# ws2812esp32_v1_0.net
KiCad netlist of a schematic drawn in Altium Designer
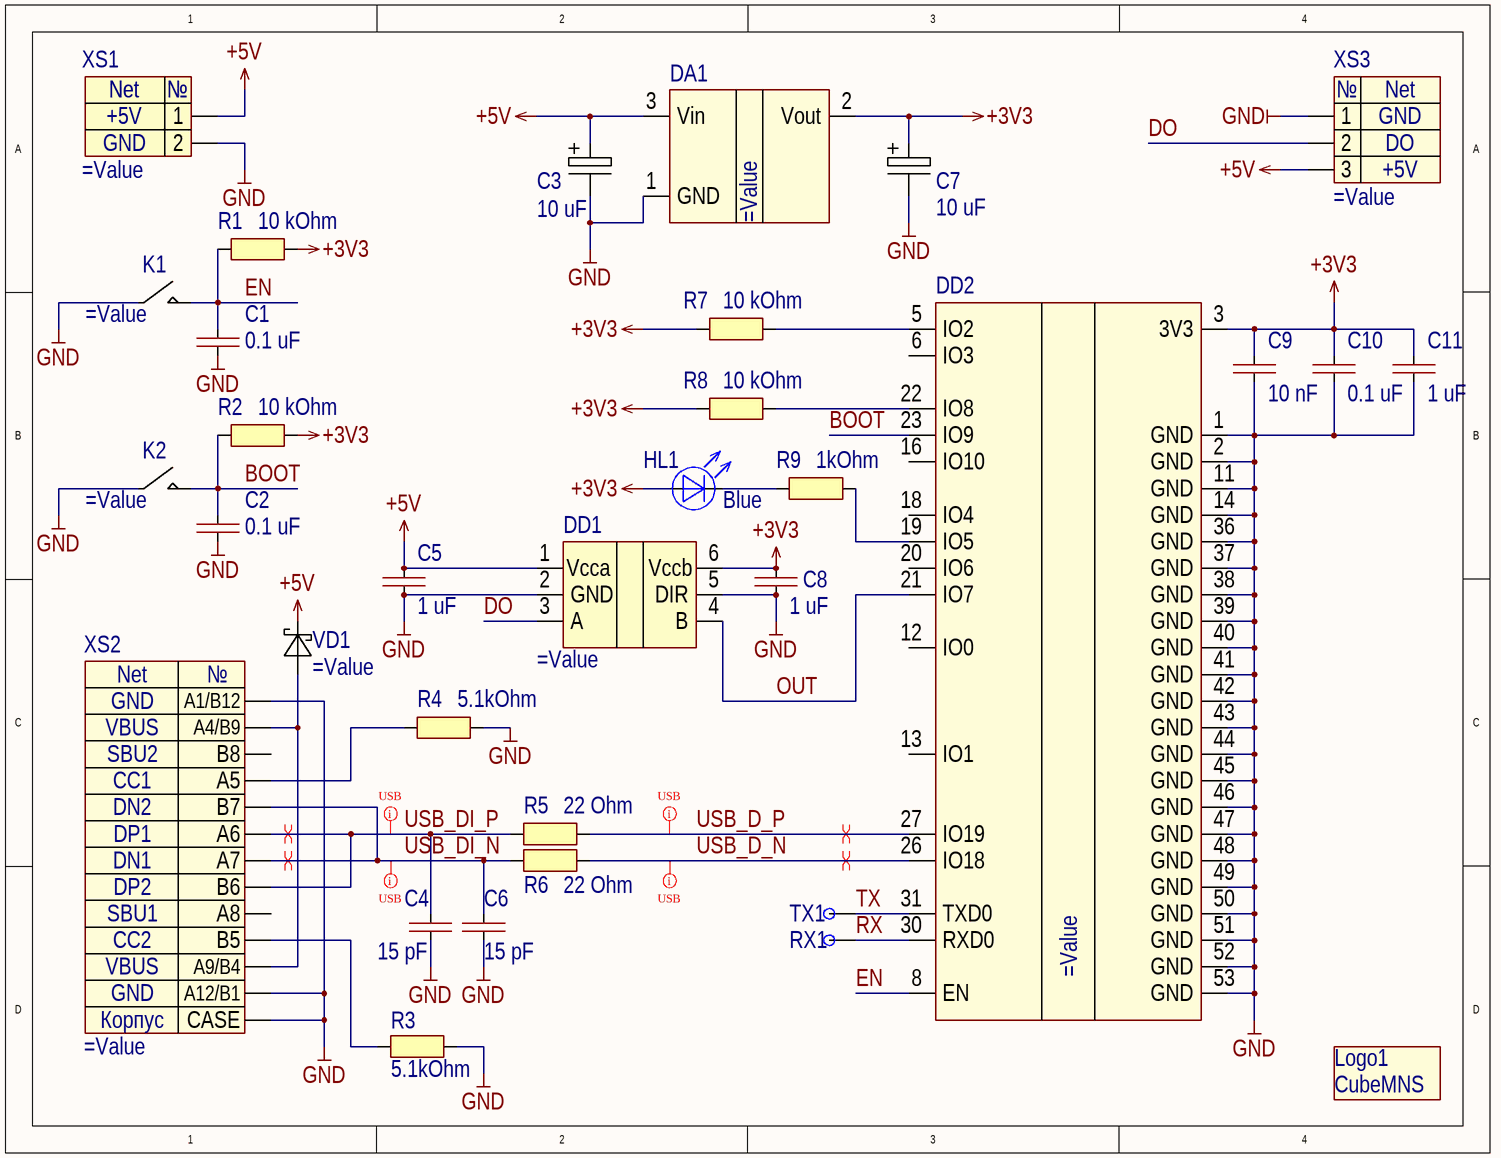
[diagram p0: ws2812esp32_v1.0.SchDoc]

(export (version "E")
  (design (tool "Eeschema 10.0.6"))
  (components
    (comp (ref "C1")
      (value "0.1 uF")
      (footprint "C0402")
      (description "CAP CER 0.1UF 50V X7R 0402")
      (fields (field (name "PART NUMBER") "GRM155R71H104KE14D") (field (name "TOLERANCE") "10"))
      (libsource (lib "ws2812esp32_v1.0_Schlib") (part "C0402 0.1uF 10% 25V"))
    )
    (comp (ref "C2")
      (value "0.1 uF")
      (footprint "C0402")
      (description "CAP CER 0.1UF 50V X7R 0402")
      (fields (field (name "PART NUMBER") "GRM155R71H104KE14D") (field (name "TOLERANCE") "10"))
      (libsource (lib "ws2812esp32_v1.0_Schlib") (part "C0402 0.1uF 10% 25V"))
    )
    (comp (ref "C3")
      (value "10 uF")
      (footprint "C tantalin Type A")
      (description "CAP TANT 10UF 10% 10V 1206")
      (fields (field (name "PART NUMBER") "T491A106K010AT") (field (name "TOLERANCE") "10%"))
      (libsource (lib "ws2812esp32_v1.0_Schlib") (part "C tantalum type A 10uF"))
    )
    (comp (ref "C4")
      (value "15 pF")
      (footprint "C0402")
      (description "CAP CER 15PF 50V C0G/NP0 0402")
      (fields (field (name "PART NUMBER") "GRM1555C1H150JA01D") (field (name "TOLERANCE") "5"))
      (libsource (lib "ws2812esp32_v1.0_Schlib") (part "C0402 15pF 5% 25V"))
    )
    (comp (ref "C5")
      (value "1 uF")
      (footprint "C0402")
      (description "CAP CER 1UF 25V X5R 0402")
      (fields (field (name "PART NUMBER") "GRM155R61E105KA12D") (field (name "VOLTAGE") "25V"))
      (libsource (lib "ws2812esp32_v1.0_Schlib") (part "C0402 1uF 10% 25V"))
    )
    (comp (ref "C6")
      (value "15 pF")
      (footprint "C0402")
      (description "CAP CER 15PF 50V C0G/NP0 0402")
      (fields (field (name "PART NUMBER") "GRM1555C1H150JA01D") (field (name "TOLERANCE") "5"))
      (libsource (lib "ws2812esp32_v1.0_Schlib") (part "C0402 15pF 5% 25V"))
    )
    (comp (ref "C7")
      (value "10 uF")
      (footprint "C tantalin Type A")
      (description "CAP TANT 10UF 10% 10V 1206")
      (fields (field (name "PART NUMBER") "T491A106K010AT") (field (name "TOLERANCE") "10%"))
      (libsource (lib "ws2812esp32_v1.0_Schlib") (part "C tantalum type A 10uF"))
    )
    (comp (ref "C8")
      (value "1 uF")
      (footprint "C0402")
      (description "CAP CER 1UF 25V X5R 0402")
      (fields (field (name "PART NUMBER") "GRM155R61E105KA12D") (field (name "VOLTAGE") "25V"))
      (libsource (lib "ws2812esp32_v1.0_Schlib") (part "C0402 1uF 10% 25V"))
    )
    (comp (ref "C9")
      (value "10 nF")
      (footprint "C0402")
      (description "CAP CER 10000PF 25V X7R 0402")
      (fields (field (name "PART NUMBER") "GRM155R71E103KA01D") (field (name "TOLERANCE") "10%"))
      (libsource (lib "ws2812esp32_v1.0_Schlib") (part "C0402 10nF 10% 25V"))
    )
    (comp (ref "C10")
      (value "0.1 uF")
      (footprint "C0402")
      (description "CAP CER 0.1UF 50V X7R 0402")
      (fields (field (name "PART NUMBER") "GRM155R71H104KE14D") (field (name "TOLERANCE") "10"))
      (libsource (lib "ws2812esp32_v1.0_Schlib") (part "C0402 0.1uF 10% 25V"))
    )
    (comp (ref "C11")
      (value "1 uF")
      (footprint "C0402")
      (description "CAP CER 1UF 25V X5R 0402")
      (fields (field (name "PART NUMBER") "GRM155R61E105KA12D") (field (name "VOLTAGE") "25V"))
      (libsource (lib "ws2812esp32_v1.0_Schlib") (part "C0402 1uF 10% 25V"))
    )
    (comp (ref "DA1")
      (value "~")
      (footprint "SOT223")
      (description "IC REG LINEAR 3.3V 1A SOT223-3")
      (fields (field (name "PART NUMBER") "LM1117GS-3.3") (field (name "VOLTAGE") "+3.3V"))
      (libsource (lib "ws2812esp32_v1.0_Schlib") (part "LM1117GS-3.3"))
    )
    (comp (ref "DD1")
      (value "~")
      (footprint "SC-70-6")
      (description "IC TRANSLTR BIDIRECTIONAL SC70-6")
      (fields (field (name "PART NUMBER") "SN74LVC1T45DCK") (field (name "VOLTAGE") "+5.5V"))
      (libsource (lib "ws2812esp32_v1.0_Schlib") (part "SN74LVC1T45DCK"))
    )
    (comp (ref "DD2")
      (value "~")
      (footprint "ESP32-C3-MINI-1")
      (description "RF TXRX MODULE BT PCB TRACE SMD")
      (fields (field (name "PART NUMBER") "ESP32-C3-MINI-1") (field (name "VOLTAGE") "+3.3V"))
      (libsource (lib "ws2812esp32_v1.0_Schlib") (part "ESP32-C3-MINI-1"))
    )
    (comp (ref "HL1")
      (value "Blue")
      (footprint "LED0603")
      (description "LED 0603 Blue")
      (fields (field (name "PART NUMBER") "APT1608QBC/D") (field (name "VOLTAGE") "4V"))
      (libsource (lib "ws2812esp32_v1.0_Schlib") (part "LED 0603 Blue"))
    )
    (comp (ref "K1")
      (value "~")
      (footprint "B3U-1000P-B")
      (description "SWITCH TACTILE SPST-NO 0.05A 12V")
      (fields (field (name "PART NUMBER") "B3U-1000P-B"))
      (libsource (lib "ws2812esp32_v1.0_Schlib") (part "B3U-1000P-B"))
    )
    (comp (ref "K2")
      (value "~")
      (footprint "B3U-1000P-B")
      (description "SWITCH TACTILE SPST-NO 0.05A 12V")
      (fields (field (name "PART NUMBER") "B3U-1000P-B"))
      (libsource (lib "ws2812esp32_v1.0_Schlib") (part "B3U-1000P-B"))
    )
    (comp (ref "Logo1")
      (value "CubeMNS")
      (footprint "CubeMNS")
      (libsource (lib "ws2812esp32_v1.0_Schlib") (part "CubeMNS"))
    )
    (comp (ref "R1")
      (value "10 kOhm")
      (footprint "R0402")
      (description "RES 10K OHM 1/16W 1% 0402 SMD")
      (fields (field (name "PART NUMBER") "RC0402FR-0710KL") (field (name "TOLERANCE") "1%"))
      (libsource (lib "ws2812esp32_v1.0_Schlib") (part "R0402 10kOhm 1%"))
    )
    (comp (ref "R2")
      (value "10 kOhm")
      (footprint "R0402")
      (description "RES 10K OHM 1/16W 1% 0402 SMD")
      (fields (field (name "PART NUMBER") "RC0402FR-0710KL") (field (name "TOLERANCE") "1%"))
      (libsource (lib "ws2812esp32_v1.0_Schlib") (part "R0402 10kOhm 1%"))
    )
    (comp (ref "R3")
      (value "5.1kOhm")
      (footprint "R0402")
      (description "RES 5.1K OHM 1/16W 1% 0402 SMD")
      (fields (field (name "PART NUMBER") "RC0402FR-075K1L") (field (name "TOLERANCE") "1%"))
      (libsource (lib "ws2812esp32_v1.0_Schlib") (part "R0402 5.1kOhm 1%"))
    )
    (comp (ref "R4")
      (value "5.1kOhm")
      (footprint "R0402")
      (description "RES 5.1K OHM 1/16W 1% 0402 SMD")
      (fields (field (name "PART NUMBER") "RC0402FR-075K1L") (field (name "TOLERANCE") "1%"))
      (libsource (lib "ws2812esp32_v1.0_Schlib") (part "R0402 5.1kOhm 1%"))
    )
    (comp (ref "R5")
      (value "22 Ohm")
      (footprint "R0402")
      (description "RES 22 OHM 1/16W 1% 0402 SMD")
      (fields (field (name "PART NUMBER") "RC0402FR-0722RL") (field (name "TOLERANCE") "1%"))
      (libsource (lib "ws2812esp32_v1.0_Schlib") (part "R0402 22Ohm 1%"))
    )
    (comp (ref "R6")
      (value "22 Ohm")
      (footprint "R0402")
      (description "RES 22 OHM 1/16W 1% 0402 SMD")
      (fields (field (name "PART NUMBER") "RC0402FR-0722RL") (field (name "TOLERANCE") "1%"))
      (libsource (lib "ws2812esp32_v1.0_Schlib") (part "R0402 22Ohm 1%"))
    )
    (comp (ref "R7")
      (value "10 kOhm")
      (footprint "R0402")
      (description "RES 10K OHM 1/16W 1% 0402 SMD")
      (fields (field (name "PART NUMBER") "RC0402FR-0710KL") (field (name "TOLERANCE") "1%"))
      (libsource (lib "ws2812esp32_v1.0_Schlib") (part "R0402 10kOhm 1%"))
    )
    (comp (ref "R8")
      (value "10 kOhm")
      (footprint "R0402")
      (description "RES 10K OHM 1/16W 1% 0402 SMD")
      (fields (field (name "PART NUMBER") "RC0402FR-0710KL") (field (name "TOLERANCE") "1%"))
      (libsource (lib "ws2812esp32_v1.0_Schlib") (part "R0402 10kOhm 1%"))
    )
    (comp (ref "R9")
      (value "1kOhm")
      (footprint "R0402")
      (description "RES 1K OHM 1/16W 1% 0402 SMD")
      (fields (field (name "PART NUMBER") "RC0402FR-071KL") (field (name "TOLERANCE") "1%"))
      (libsource (lib "ws2812esp32_v1.0_Schlib") (part "R0402 1kOhm 1%"))
    )
    (comp (ref "RX1")
      (value "~")
      (footprint "СontactPad0.5")
      (description "Round 0.5 mm")
      (libsource (lib "ws2812esp32_v1.0_Schlib") (part "Сontact Pad"))
    )
    (comp (ref "TX1")
      (value "~")
      (footprint "СontactPad0.5")
      (description "Round 0.5 mm")
      (libsource (lib "ws2812esp32_v1.0_Schlib") (part "Сontact Pad"))
    )
    (comp (ref "VD1")
      (value "~")
      (footprint "SOD-123F")
      (description "DIODE SCHOTTKY 40V 1A")
      (fields (field (name "PART NUMBER") "DSK14") (field (name "VOLTAGE") "40V"))
      (libsource (lib "ws2812esp32_v1.0_Schlib") (part "DSK14"))
    )
    (comp (ref "XS1")
      (value "~")
      (footprint "FLTS22WR00")
      (description "SMD TERMINAL BLOCK 2 PIN")
      (fields (field (name "PART NUMBER") "FLTS22WR00") (field (name "VOLTAGE") "250V"))
      (libsource (lib "ws2812esp32_v1.0_Schlib") (part "FLTS22WR00"))
    )
    (comp (ref "XS2")
      (value "~")
      (footprint "USB4110-GF-A")
      (description "CONN RCP USB2.0 TYP C 24P SMD RA")
      (fields (field (name "PART NUMBER") "USB4110-GF-A") (field (name "VOLTAGE") "48V"))
      (libsource (lib "ws2812esp32_v1.0_Schlib") (part "USB4110-GF-A"))
    )
    (comp (ref "XS3")
      (value "~")
      (footprint "FLTS32WR00")
      (description "SMD TERMINAL BLOCK 3 PIN")
      (fields (field (name "PART NUMBER") "FLTS32WR00") (field (name "VOLTAGE") "250V"))
      (libsource (lib "ws2812esp32_v1.0_Schlib") (part "FLTS32WR00"))
    )
  )
  (nets
    (net (code "1") (name "+3V3") (class "Default")
      (node (ref "C10") (pin "2") (pinfunction "2_2") (pintype "passive"))
      (node (ref "C11") (pin "2") (pinfunction "2_2") (pintype "passive"))
      (node (ref "C7") (pin "1") (pinfunction "+_1") (pintype "passive"))
      (node (ref "C8") (pin "2") (pinfunction "2_2") (pintype "passive"))
      (node (ref "C9") (pin "2") (pinfunction "2_2") (pintype "passive"))
      (node (ref "DA1") (pin "2") (pinfunction "Vout_2") (pintype "passive"))
      (node (ref "DD1") (pin "6") (pinfunction "Vccb_6") (pintype "passive"))
      (node (ref "DD2") (pin "3") (pinfunction "3V3_3") (pintype "passive"))
      (node (ref "HL1") (pin "2") (pinfunction "+_2") (pintype "passive"))
      (node (ref "R1") (pin "1") (pinfunction "1_1") (pintype "passive"))
      (node (ref "R2") (pin "1") (pinfunction "1_1") (pintype "passive"))
      (node (ref "R7") (pin "2") (pinfunction "2_2") (pintype "passive"))
      (node (ref "R8") (pin "2") (pinfunction "2_2") (pintype "passive"))
    )
    (net (code "2") (name "+5V") (class "Default")
      (node (ref "C3") (pin "1") (pinfunction "+_1") (pintype "passive"))
      (node (ref "C5") (pin "2") (pinfunction "2_2") (pintype "passive"))
      (node (ref "DA1") (pin "3") (pinfunction "Vin_3") (pintype "passive"))
      (node (ref "DD1") (pin "1") (pinfunction "Vcca_1") (pintype "passive"))
      (node (ref "VD1") (pin "1") (pinfunction "-_1") (pintype "passive"))
      (node (ref "XS1") (pin "1") (pinfunction "1_1") (pintype "passive"))
      (node (ref "XS3") (pin "3") (pinfunction "3_3") (pintype "passive"))
    )
    (net (code "3") (name "/BOOT") (class "Default")
      (node (ref "C2") (pin "2") (pinfunction "2_2") (pintype "passive"))
      (node (ref "DD2") (pin "23") (pinfunction "IO9_23") (pintype "passive"))
      (node (ref "K2") (pin "2") (pinfunction "2_2") (pintype "passive"))
      (node (ref "R2") (pin "2") (pinfunction "2_2") (pintype "passive"))
    )
    (net (code "4") (name "/DO") (class "Default")
      (node (ref "DD1") (pin "3") (pinfunction "A_3") (pintype "passive"))
      (node (ref "XS3") (pin "2") (pinfunction "2_2") (pintype "passive"))
    )
    (net (code "5") (name "/EN") (class "Default")
      (node (ref "C1") (pin "2") (pinfunction "2_2") (pintype "passive"))
      (node (ref "DD2") (pin "8") (pinfunction "EN_8") (pintype "passive"))
      (node (ref "K1") (pin "2") (pinfunction "2_2") (pintype "passive"))
      (node (ref "R1") (pin "2") (pinfunction "2_2") (pintype "passive"))
    )
    (net (code "6") (name "/OUT") (class "Default")
      (node (ref "DD1") (pin "4") (pinfunction "B_4") (pintype "passive"))
      (node (ref "DD2") (pin "21") (pinfunction "IO7_21") (pintype "passive"))
    )
    (net (code "7") (name "/RX") (class "Default")
      (node (ref "DD2") (pin "30") (pinfunction "RXD0_30") (pintype "passive"))
      (node (ref "RX1") (pin "1") (pinfunction "1_1") (pintype "passive"))
    )
    (net (code "8") (name "/TX") (class "Default")
      (node (ref "DD2") (pin "31") (pinfunction "TXD0_31") (pintype "passive"))
      (node (ref "TX1") (pin "1") (pinfunction "1_1") (pintype "passive"))
    )
    (net (code "9") (name "/USB_DI_N") (class "Default")
      (node (ref "C6") (pin "2") (pinfunction "2_2") (pintype "passive"))
      (node (ref "R6") (pin "1") (pinfunction "1_1") (pintype "passive"))
      (node (ref "XS2") (pin "A7") (pinfunction "A7_A7") (pintype "passive"))
      (node (ref "XS2") (pin "B7") (pinfunction "B7_B7") (pintype "passive"))
    )
    (net (code "10") (name "/USB_DI_P") (class "Default")
      (node (ref "C4") (pin "2") (pinfunction "2_2") (pintype "passive"))
      (node (ref "R5") (pin "1") (pinfunction "1_1") (pintype "passive"))
      (node (ref "XS2") (pin "A6") (pinfunction "A6_A6") (pintype "passive"))
      (node (ref "XS2") (pin "B6") (pinfunction "B6_B6") (pintype "passive"))
    )
    (net (code "11") (name "/USB_D_N") (class "Default")
      (node (ref "DD2") (pin "26") (pinfunction "IO18_26") (pintype "passive"))
      (node (ref "R6") (pin "2") (pinfunction "2_2") (pintype "passive"))
    )
    (net (code "12") (name "/USB_D_P") (class "Default")
      (node (ref "DD2") (pin "27") (pinfunction "IO19_27") (pintype "passive"))
      (node (ref "R5") (pin "2") (pinfunction "2_2") (pintype "passive"))
    )
    (net (code "13") (name "GND") (class "Default")
      (node (ref "C1") (pin "1") (pinfunction "1_1") (pintype "passive"))
      (node (ref "C10") (pin "1") (pinfunction "1_1") (pintype "passive"))
      (node (ref "C11") (pin "1") (pinfunction "1_1") (pintype "passive"))
      (node (ref "C2") (pin "1") (pinfunction "1_1") (pintype "passive"))
      (node (ref "C3") (pin "2") (pinfunction "-_2") (pintype "passive"))
      (node (ref "C4") (pin "1") (pinfunction "1_1") (pintype "passive"))
      (node (ref "C5") (pin "1") (pinfunction "1_1") (pintype "passive"))
      (node (ref "C6") (pin "1") (pinfunction "1_1") (pintype "passive"))
      (node (ref "C7") (pin "2") (pinfunction "-_2") (pintype "passive"))
      (node (ref "C8") (pin "1") (pinfunction "1_1") (pintype "passive"))
      (node (ref "C9") (pin "1") (pinfunction "1_1") (pintype "passive"))
      (node (ref "DA1") (pin "1") (pinfunction "GND_1") (pintype "passive"))
      (node (ref "DD1") (pin "2") (pinfunction "GND_2") (pintype "passive"))
      (node (ref "DD1") (pin "5") (pinfunction "DIR_5") (pintype "passive"))
      (node (ref "DD2") (pin "1") (pinfunction "GND_1") (pintype "passive"))
      (node (ref "DD2") (pin "11") (pinfunction "GND_11") (pintype "passive"))
      (node (ref "DD2") (pin "14") (pinfunction "GND_14") (pintype "passive"))
      (node (ref "DD2") (pin "2") (pinfunction "GND_2") (pintype "passive"))
      (node (ref "DD2") (pin "36") (pinfunction "GND_36") (pintype "passive"))
      (node (ref "DD2") (pin "37") (pinfunction "GND_37") (pintype "passive"))
      (node (ref "DD2") (pin "38") (pinfunction "GND_38") (pintype "passive"))
      (node (ref "DD2") (pin "39") (pinfunction "GND_39") (pintype "passive"))
      (node (ref "DD2") (pin "40") (pinfunction "GND_40") (pintype "passive"))
      (node (ref "DD2") (pin "41") (pinfunction "GND_41") (pintype "passive"))
      (node (ref "DD2") (pin "42") (pinfunction "GND_42") (pintype "passive"))
      (node (ref "DD2") (pin "43") (pinfunction "GND_43") (pintype "passive"))
      (node (ref "DD2") (pin "44") (pinfunction "GND_44") (pintype "passive"))
      (node (ref "DD2") (pin "45") (pinfunction "GND_45") (pintype "passive"))
      (node (ref "DD2") (pin "46") (pinfunction "GND_46") (pintype "passive"))
      (node (ref "DD2") (pin "47") (pinfunction "GND_47") (pintype "passive"))
      (node (ref "DD2") (pin "48") (pinfunction "GND_48") (pintype "passive"))
      (node (ref "DD2") (pin "49") (pinfunction "GND_49") (pintype "passive"))
      (node (ref "DD2") (pin "50") (pinfunction "GND_50") (pintype "passive"))
      (node (ref "DD2") (pin "51") (pinfunction "GND_51") (pintype "passive"))
      (node (ref "DD2") (pin "52") (pinfunction "GND_52") (pintype "passive"))
      (node (ref "DD2") (pin "53") (pinfunction "GND_53") (pintype "passive"))
      (node (ref "K1") (pin "1") (pinfunction "1_1") (pintype "passive"))
      (node (ref "K2") (pin "1") (pinfunction "1_1") (pintype "passive"))
      (node (ref "R3") (pin "2") (pinfunction "2_2") (pintype "passive"))
      (node (ref "R4") (pin "2") (pinfunction "2_2") (pintype "passive"))
      (node (ref "XS1") (pin "2") (pinfunction "2_2") (pintype "passive"))
      (node (ref "XS2") (pin "0") (pinfunction "CASE_0") (pintype "passive"))
      (node (ref "XS2") (pin "A1/B12") (pinfunction "A1/B12_A1/B12") (pintype "passive"))
      (node (ref "XS2") (pin "A12/B1") (pinfunction "A12/B1_A12/B1") (pintype "passive"))
      (node (ref "XS3") (pin "1") (pinfunction "1_1") (pintype "passive"))
    )
    (net (code "14") (name "Net-(DD2-IO2)") (class "Default")
      (node (ref "DD2") (pin "5") (pinfunction "IO2_5") (pintype "passive"))
      (node (ref "R7") (pin "1") (pinfunction "1_1") (pintype "passive"))
    )
    (net (code "15") (name "Net-(DD2-IO5)") (class "Default")
      (node (ref "DD2") (pin "19") (pinfunction "IO5_19") (pintype "passive"))
      (node (ref "R9") (pin "2") (pinfunction "2_2") (pintype "passive"))
    )
    (net (code "16") (name "Net-(DD2-IO8)") (class "Default")
      (node (ref "DD2") (pin "22") (pinfunction "IO8_22") (pintype "passive"))
      (node (ref "R8") (pin "1") (pinfunction "1_1") (pintype "passive"))
    )
    (net (code "17") (name "Net-(HL1--)") (class "Default")
      (node (ref "HL1") (pin "1") (pinfunction "-_1") (pintype "passive"))
      (node (ref "R9") (pin "1") (pinfunction "1_1") (pintype "passive"))
    )
    (net (code "18") (name "Net-(R3-Pad1)") (class "Default")
      (node (ref "R3") (pin "1") (pinfunction "1_1") (pintype "passive"))
      (node (ref "XS2") (pin "B5") (pinfunction "B5_B5") (pintype "passive"))
    )
    (net (code "19") (name "Net-(R4-Pad1)") (class "Default")
      (node (ref "R4") (pin "1") (pinfunction "1_1") (pintype "passive"))
      (node (ref "XS2") (pin "A5") (pinfunction "A5_A5") (pintype "passive"))
    )
    (net (code "20") (name "Net-(VD1-+)") (class "Default")
      (node (ref "VD1") (pin "2") (pinfunction "+_2") (pintype "passive"))
      (node (ref "XS2") (pin "A4/B9") (pinfunction "A4/B9_A4/B9") (pintype "passive"))
      (node (ref "XS2") (pin "A9/B4") (pinfunction "A9/B4_A9/B4") (pintype "passive"))
    )
    (net (code "21") (name "unconnected-(DD2-IO0-Pad12)") (class "Default")
      (node (ref "DD2") (pin "12") (pinfunction "IO0_12") (pintype "passive"))
    )
    (net (code "22") (name "unconnected-(DD2-IO1-Pad13)") (class "Default")
      (node (ref "DD2") (pin "13") (pinfunction "IO1_13") (pintype "passive"))
    )
    (net (code "23") (name "unconnected-(DD2-IO3-Pad6)") (class "Default")
      (node (ref "DD2") (pin "6") (pinfunction "IO3_6") (pintype "passive"))
    )
    (net (code "24") (name "unconnected-(DD2-IO4-Pad18)") (class "Default")
      (node (ref "DD2") (pin "18") (pinfunction "IO4_18") (pintype "passive"))
    )
    (net (code "25") (name "unconnected-(DD2-IO6-Pad20)") (class "Default")
      (node (ref "DD2") (pin "20") (pinfunction "IO6_20") (pintype "passive"))
    )
    (net (code "26") (name "unconnected-(DD2-IO10-Pad16)") (class "Default")
      (node (ref "DD2") (pin "16") (pinfunction "IO10_16") (pintype "passive"))
    )
    (net (code "27") (name "unconnected-(XS2-PadA8)") (class "Default")
      (node (ref "XS2") (pin "A8") (pinfunction "A8_A8") (pintype "passive"))
    )
    (net (code "28") (name "unconnected-(XS2-PadB8)") (class "Default")
      (node (ref "XS2") (pin "B8") (pinfunction "B8_B8") (pintype "passive"))
    )
  )
)
